# circle.net
KiCad netlist of a schematic drawn in EAGLE
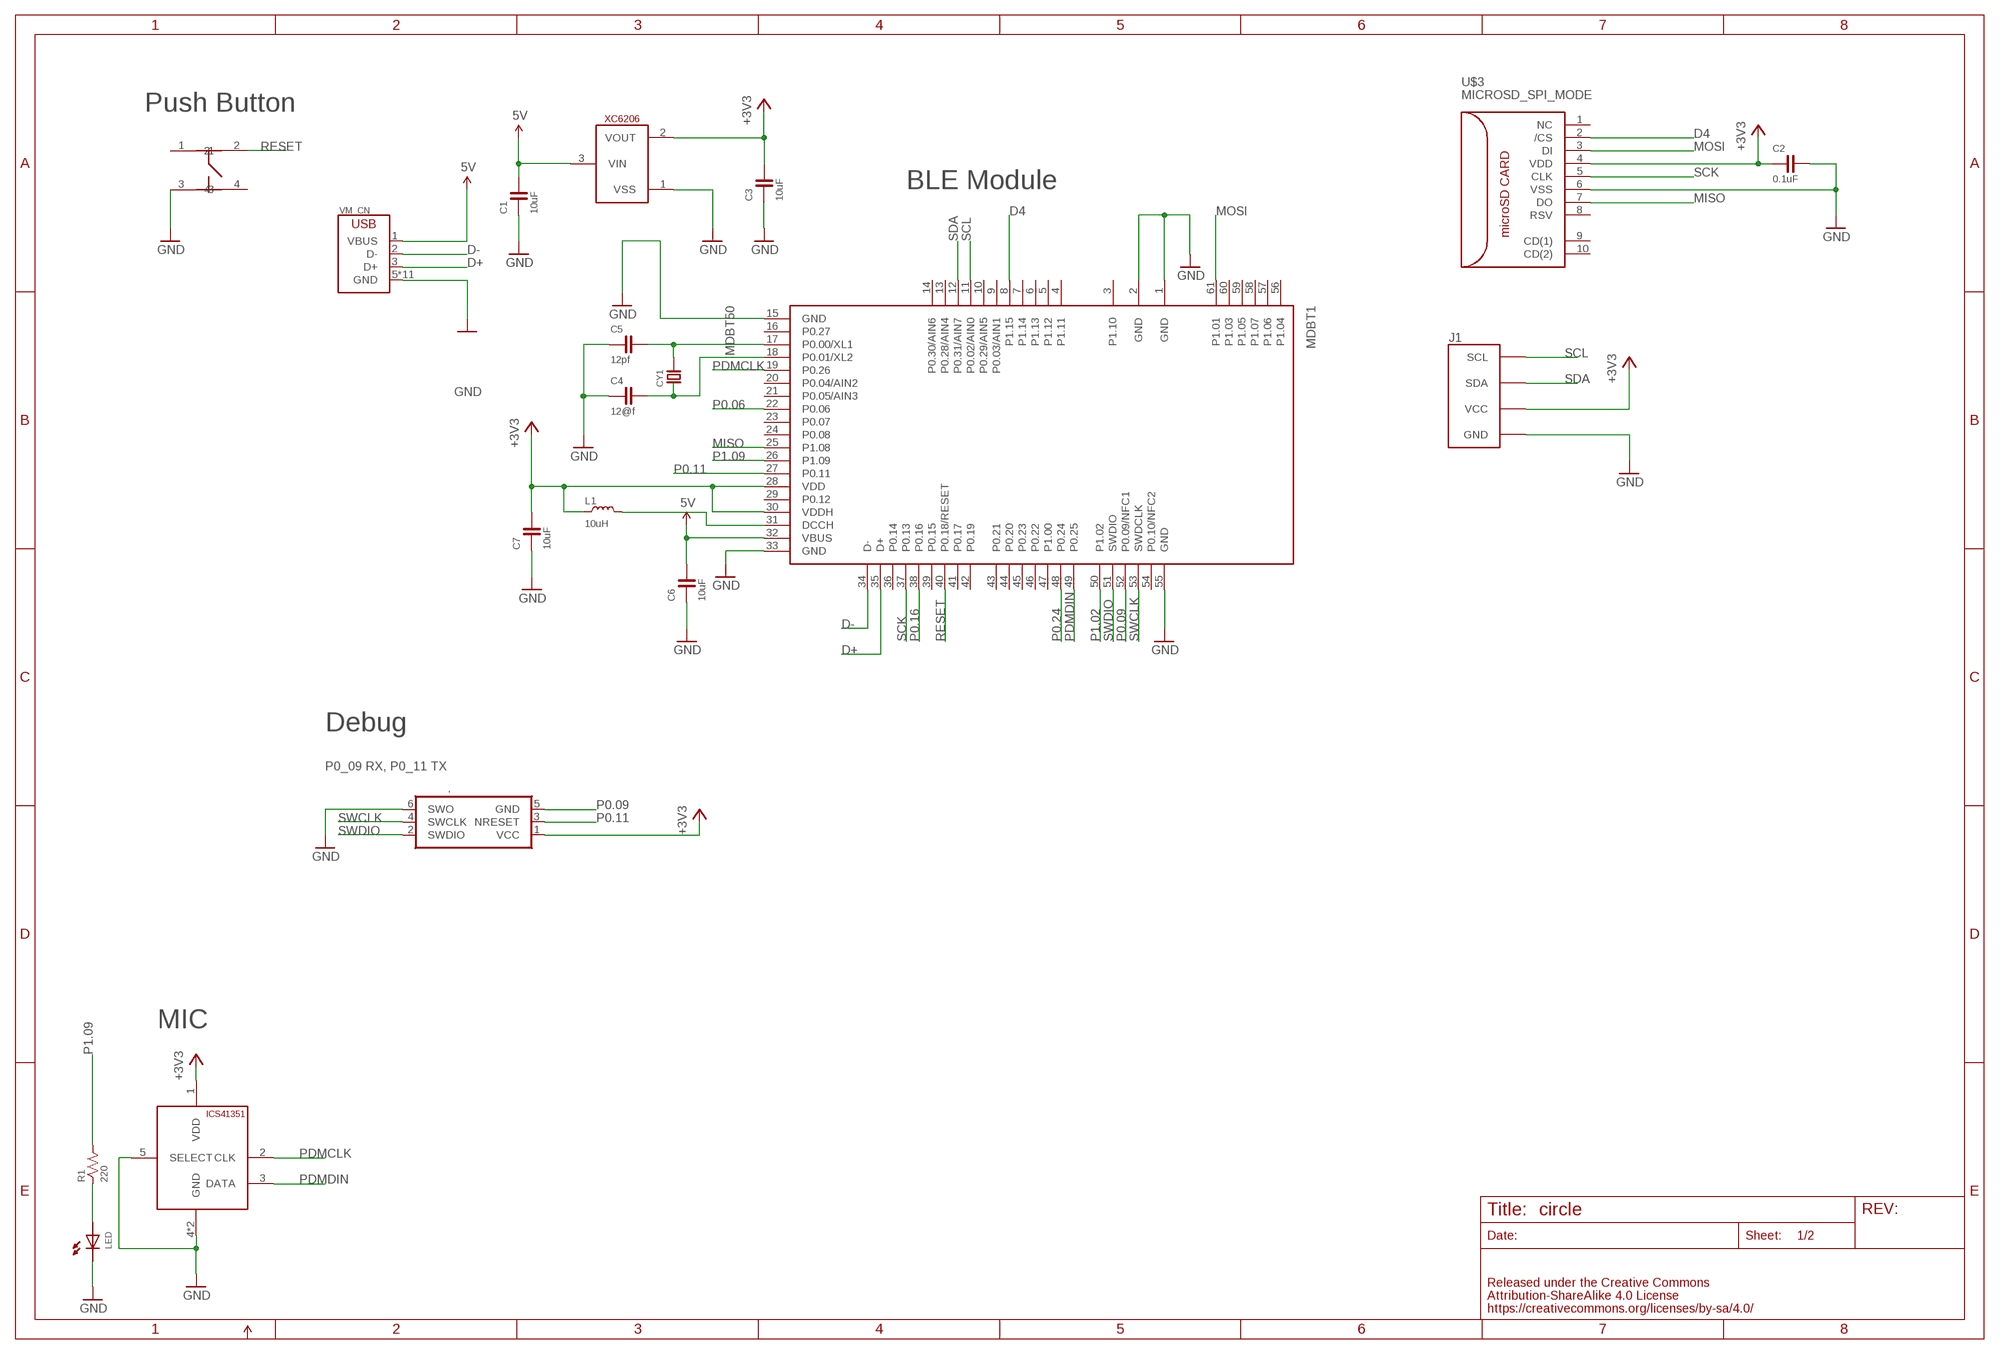
[diagram p0: schematic, sheet 1]
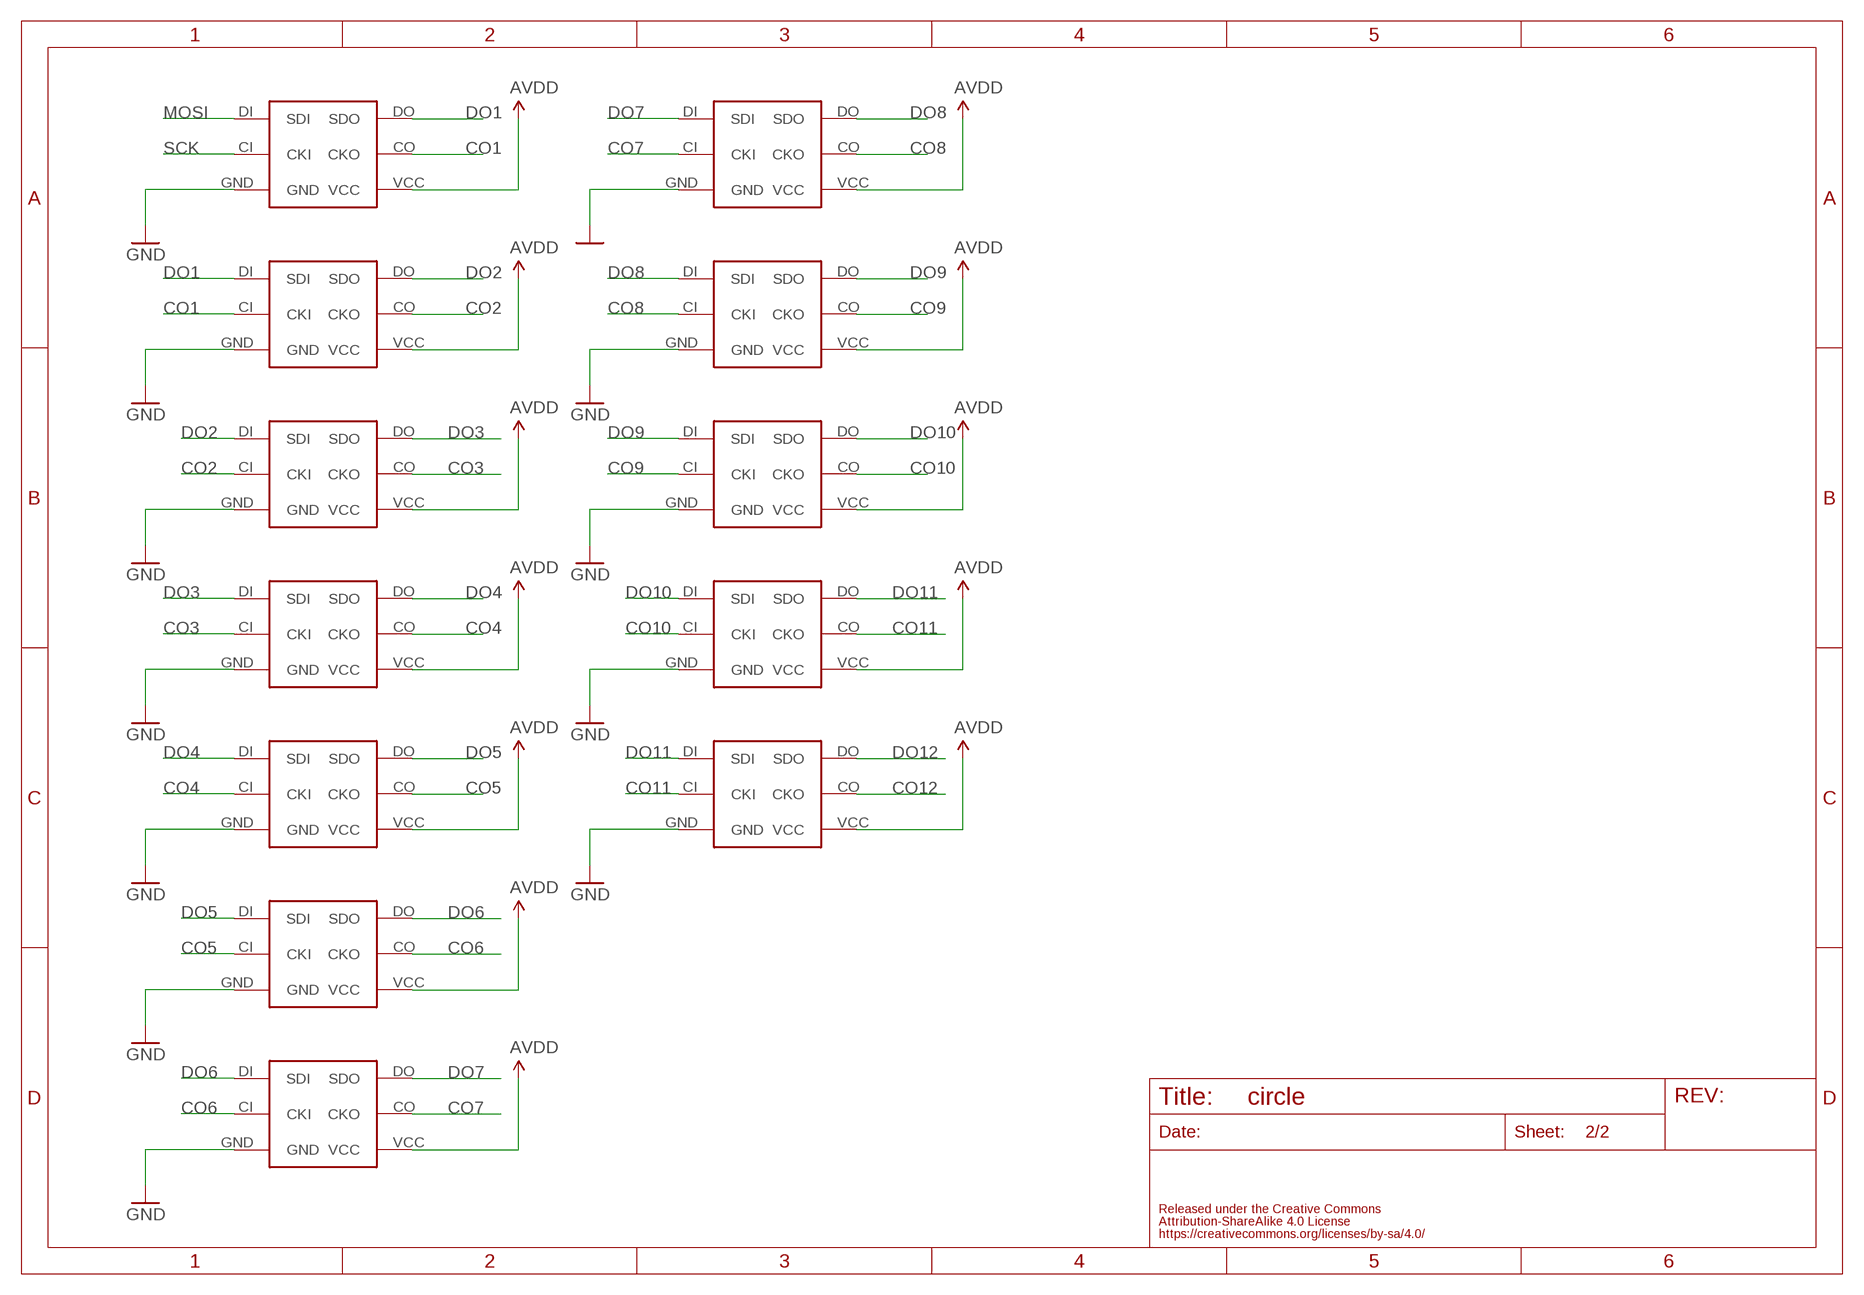
[diagram p1: schematic, sheet 2]

(export (version "E")
  (design (tool "Eeschema 10.0.6"))
  (components
    (comp (ref "0")
      (value "APA102_IPIXEL")
      (footprint "eagle-import:APA102(IPIXEL)")
      (libsource (lib "eagle-import") (part "APA102_IPIXEL"))
    )
    (comp (ref "1")
      (value "APA102_IPIXEL")
      (footprint "eagle-import:APA102(IPIXEL)")
      (libsource (lib "eagle-import") (part "APA102_IPIXEL"))
    )
    (comp (ref "2")
      (value "APA102_IPIXEL")
      (footprint "eagle-import:APA102(IPIXEL)")
      (libsource (lib "eagle-import") (part "APA102_IPIXEL"))
    )
    (comp (ref "3")
      (value "APA102_IPIXEL")
      (footprint "eagle-import:APA102(IPIXEL)")
      (libsource (lib "eagle-import") (part "APA102_IPIXEL"))
    )
    (comp (ref "4")
      (value "APA102_IPIXEL")
      (footprint "eagle-import:APA102(IPIXEL)")
      (libsource (lib "eagle-import") (part "APA102_IPIXEL"))
    )
    (comp (ref "5")
      (value "APA102_IPIXEL")
      (footprint "eagle-import:APA102(IPIXEL)")
      (libsource (lib "eagle-import") (part "APA102_IPIXEL"))
    )
    (comp (ref "6")
      (value "APA102_IPIXEL")
      (footprint "eagle-import:APA102(IPIXEL)")
      (libsource (lib "eagle-import") (part "APA102_IPIXEL"))
    )
    (comp (ref "7")
      (value "APA102_IPIXEL")
      (footprint "eagle-import:APA102(IPIXEL)")
      (libsource (lib "eagle-import") (part "APA102_IPIXEL"))
    )
    (comp (ref "8")
      (value "APA102_IPIXEL")
      (footprint "eagle-import:APA102(IPIXEL)")
      (libsource (lib "eagle-import") (part "APA102_IPIXEL"))
    )
    (comp (ref "9")
      (value "APA102_IPIXEL")
      (footprint "eagle-import:APA102(IPIXEL)")
      (libsource (lib "eagle-import") (part "APA102_IPIXEL"))
    )
    (comp (ref "10")
      (value "APA102_IPIXEL")
      (footprint "eagle-import:APA102(IPIXEL)")
      (libsource (lib "eagle-import") (part "APA102_IPIXEL"))
    )
    (comp (ref "11")
      (value "APA102_IPIXEL")
      (footprint "eagle-import:APA102(IPIXEL)")
      (libsource (lib "eagle-import") (part "APA102_IPIXEL"))
    )
    (comp (ref ".")
      (value "TC2030-IDC-NL")
      (footprint "eagle-import:TC2030-IDC-NL")
      (libsource (lib "eagle-import") (part "TC2030-IDC-NL"))
    )
    (comp (ref "C1")
      (value "10uF")
      (footprint "eagle-import:0603")
      (libsource (lib "eagle-import") (part "CAPACITOR-0603"))
    )
    (comp (ref "C2")
      (value "0.1uF")
      (footprint "eagle-import:0603")
      (libsource (lib "eagle-import") (part "CAPACITOR-0603"))
    )
    (comp (ref "C3")
      (value "10uF")
      (footprint "eagle-import:0603")
      (libsource (lib "eagle-import") (part "CAPACITOR-0603"))
    )
    (comp (ref "C4")
      (value "12@f")
      (footprint "eagle-import:0603")
      (libsource (lib "eagle-import") (part "CAPACITOR-0603"))
    )
    (comp (ref "C5")
      (value "12pf")
      (footprint "eagle-import:0603")
      (libsource (lib "eagle-import") (part "CAPACITOR-0603"))
    )
    (comp (ref "C6")
      (value "10uF")
      (footprint "eagle-import:0603")
      (libsource (lib "eagle-import") (part "CAPACITOR-0603"))
    )
    (comp (ref "C7")
      (value "10uF")
      (footprint "eagle-import:0603")
      (libsource (lib "eagle-import") (part "CAPACITOR-0603"))
    )
    (comp (ref "CY1")
      (value "CRYSTAL-ABS07")
      (footprint "eagle-import:ABRACON-ABS07-32.768KHZ")
      (libsource (lib "eagle-import") (part "CRYSTAL-ABS07"))
    )
    (comp (ref "IC1")
      (value "XC6206")
      (footprint "eagle-import:SOT-23")
      (libsource (lib "eagle-import") (part "XC6206"))
    )
    (comp (ref "J1")
      (value "FABO_BRICK_I2C-B04B-PASK-1")
      (footprint "eagle-import:FABO_BRICK_I2C_B04B-PASK-1")
      (libsource (lib "eagle-import") (part "FABO_BRICK_I2C-B04B-PASK-1"))
    )
    (comp (ref "L1")
      (value "10uH")
      (footprint "eagle-import:0603")
      (libsource (lib "eagle-import") (part "COIL-0603"))
    )
    (comp (ref "LED")
      (value "LED-0603")
      (footprint "eagle-import:0603")
      (libsource (lib "eagle-import") (part "LED-0603"))
    )
    (comp (ref "MDBT1")
      (value "MDBT50")
      (footprint "eagle-import:MDBT50")
      (libsource (lib "eagle-import") (part "MDBT50"))
    )
    (comp (ref "MIC1")
      (value "TDK-ICS41351")
      (footprint "eagle-import:ICS41351")
      (libsource (lib "eagle-import") (part "TDK-ICS41351"))
    )
    (comp (ref "R1")
      (value "220")
      (footprint "eagle-import:0603")
      (libsource (lib "eagle-import") (part "RESISTOR-0603"))
    )
    (comp (ref "U$3")
      (value "MICROSD_SPI_MODE")
      (footprint "eagle-import:MICRO_SD_CONNECTOR")
      (libsource (lib "eagle-import") (part "MICROSD_SPI_MODE"))
    )
    (comp (ref "U$5")
      (value "SWICTH-4P(KMR2)")
      (footprint "eagle-import:SWITCH-4P(KMR2)")
      (libsource (lib "eagle-import") (part "SWICTH-4P(KMR2)"))
    )
    (comp (ref "VM_CN")
      (value "USB-ZX62D")
      (footprint "eagle-import:ZX62D-B-5PA8")
      (libsource (lib "eagle-import") (part "USB-ZX62D"))
    )
  )
  (nets
    (net (code "1") (name "+3V3") (class "Default")
      (node (ref ".") (pin "1") (pinfunction "VCC_1") (pintype "passive"))
      (node (ref "C2") (pin "1") (pinfunction "1_1") (pintype "passive"))
      (node (ref "C3") (pin "2") (pinfunction "2_2") (pintype "passive"))
      (node (ref "C7") (pin "2") (pinfunction "2_2") (pintype "passive"))
      (node (ref "IC1") (pin "2") (pinfunction "VOUT_2") (pintype "bidirectional"))
      (node (ref "J1") (pin "VCC") (pinfunction "VCC_VCC") (pintype "bidirectional"))
      (node (ref "L1") (pin "1") (pinfunction "1_1") (pintype "bidirectional"))
      (node (ref "MDBT1") (pin "28") (pinfunction "VDD_28") (pintype "bidirectional"))
      (node (ref "MDBT1") (pin "30") (pinfunction "VDDH_30") (pintype "bidirectional"))
      (node (ref "MIC1") (pin "1") (pinfunction "VDD_1") (pintype "bidirectional"))
      (node (ref "U$3") (pin "4") (pinfunction "VDD_4") (pintype "bidirectional"))
    )
    (net (code "3") (name "5V") (class "Default")
      (node (ref "C1") (pin "2") (pinfunction "2_2") (pintype "passive"))
      (node (ref "C6") (pin "2") (pinfunction "2_2") (pintype "passive"))
      (node (ref "IC1") (pin "3") (pinfunction "VIN_3") (pintype "bidirectional"))
      (node (ref "MDBT1") (pin "32") (pinfunction "VBUS_32") (pintype "bidirectional"))
      (node (ref "VM_CN") (pin "1") (pinfunction "VBUS_1") (pintype "bidirectional"))
    )
    (net (code "4") (name "AVDD") (class "Default")
      (node (ref "0") (pin "VCC") (pinfunction "VCC_VCC") (pintype "bidirectional"))
      (node (ref "1") (pin "VCC") (pinfunction "VCC_VCC") (pintype "bidirectional"))
      (node (ref "10") (pin "VCC") (pinfunction "VCC_VCC") (pintype "bidirectional"))
      (node (ref "11") (pin "VCC") (pinfunction "VCC_VCC") (pintype "bidirectional"))
      (node (ref "2") (pin "VCC") (pinfunction "VCC_VCC") (pintype "bidirectional"))
      (node (ref "3") (pin "VCC") (pinfunction "VCC_VCC") (pintype "bidirectional"))
      (node (ref "4") (pin "VCC") (pinfunction "VCC_VCC") (pintype "bidirectional"))
      (node (ref "5") (pin "VCC") (pinfunction "VCC_VCC") (pintype "bidirectional"))
      (node (ref "6") (pin "VCC") (pinfunction "VCC_VCC") (pintype "bidirectional"))
      (node (ref "7") (pin "VCC") (pinfunction "VCC_VCC") (pintype "bidirectional"))
      (node (ref "8") (pin "VCC") (pinfunction "VCC_VCC") (pintype "bidirectional"))
      (node (ref "9") (pin "VCC") (pinfunction "VCC_VCC") (pintype "bidirectional"))
    )
    (net (code "5") (name "CO1") (class "Default")
      (node (ref "0") (pin "CO") (pinfunction "CKO_CO") (pintype "bidirectional"))
      (node (ref "1") (pin "CI") (pinfunction "CKI_CI") (pintype "bidirectional"))
    )
    (net (code "6") (name "CO2") (class "Default")
      (node (ref "1") (pin "CO") (pinfunction "CKO_CO") (pintype "bidirectional"))
      (node (ref "2") (pin "CI") (pinfunction "CKI_CI") (pintype "bidirectional"))
    )
    (net (code "7") (name "CO3") (class "Default")
      (node (ref "2") (pin "CO") (pinfunction "CKO_CO") (pintype "bidirectional"))
      (node (ref "3") (pin "CI") (pinfunction "CKI_CI") (pintype "bidirectional"))
    )
    (net (code "8") (name "CO4") (class "Default")
      (node (ref "3") (pin "CO") (pinfunction "CKO_CO") (pintype "bidirectional"))
      (node (ref "4") (pin "CI") (pinfunction "CKI_CI") (pintype "bidirectional"))
    )
    (net (code "9") (name "CO5") (class "Default")
      (node (ref "4") (pin "CO") (pinfunction "CKO_CO") (pintype "bidirectional"))
      (node (ref "5") (pin "CI") (pinfunction "CKI_CI") (pintype "bidirectional"))
    )
    (net (code "10") (name "CO6") (class "Default")
      (node (ref "5") (pin "CO") (pinfunction "CKO_CO") (pintype "bidirectional"))
      (node (ref "6") (pin "CI") (pinfunction "CKI_CI") (pintype "bidirectional"))
    )
    (net (code "11") (name "CO7") (class "Default")
      (node (ref "6") (pin "CO") (pinfunction "CKO_CO") (pintype "bidirectional"))
      (node (ref "7") (pin "CI") (pinfunction "CKI_CI") (pintype "bidirectional"))
    )
    (net (code "12") (name "CO8") (class "Default")
      (node (ref "7") (pin "CO") (pinfunction "CKO_CO") (pintype "bidirectional"))
      (node (ref "8") (pin "CI") (pinfunction "CKI_CI") (pintype "bidirectional"))
    )
    (net (code "13") (name "CO9") (class "Default")
      (node (ref "8") (pin "CO") (pinfunction "CKO_CO") (pintype "bidirectional"))
      (node (ref "9") (pin "CI") (pinfunction "CKI_CI") (pintype "bidirectional"))
    )
    (net (code "14") (name "CO10") (class "Default")
      (node (ref "10") (pin "CI") (pinfunction "CKI_CI") (pintype "bidirectional"))
      (node (ref "9") (pin "CO") (pinfunction "CKO_CO") (pintype "bidirectional"))
    )
    (net (code "15") (name "CO11") (class "Default")
      (node (ref "10") (pin "CO") (pinfunction "CKO_CO") (pintype "bidirectional"))
      (node (ref "11") (pin "CI") (pinfunction "CKI_CI") (pintype "bidirectional"))
    )
    (net (code "16") (name "CO12") (class "Default")
      (node (ref "11") (pin "CO") (pinfunction "CKO_CO") (pintype "bidirectional"))
    )
    (net (code "17") (name "D+") (class "Default")
      (node (ref "MDBT1") (pin "35") (pinfunction "D+_35") (pintype "bidirectional"))
      (node (ref "VM_CN") (pin "3") (pinfunction "D+_3") (pintype "bidirectional"))
    )
    (net (code "18") (name "D-") (class "Default")
      (node (ref "MDBT1") (pin "34") (pinfunction "D-_34") (pintype "bidirectional"))
      (node (ref "VM_CN") (pin "2") (pinfunction "D-_2") (pintype "bidirectional"))
    )
    (net (code "19") (name "D4") (class "Default")
      (node (ref "MDBT1") (pin "8") (pinfunction "P1.15_8") (pintype "bidirectional"))
      (node (ref "U$3") (pin "2") (pinfunction "/CS_2") (pintype "bidirectional"))
    )
    (net (code "20") (name "DO1") (class "Default")
      (node (ref "0") (pin "DO") (pinfunction "SDO_DO") (pintype "bidirectional"))
      (node (ref "1") (pin "DI") (pinfunction "SDI_DI") (pintype "bidirectional"))
    )
    (net (code "21") (name "DO2") (class "Default")
      (node (ref "1") (pin "DO") (pinfunction "SDO_DO") (pintype "bidirectional"))
      (node (ref "2") (pin "DI") (pinfunction "SDI_DI") (pintype "bidirectional"))
    )
    (net (code "22") (name "DO3") (class "Default")
      (node (ref "2") (pin "DO") (pinfunction "SDO_DO") (pintype "bidirectional"))
      (node (ref "3") (pin "DI") (pinfunction "SDI_DI") (pintype "bidirectional"))
    )
    (net (code "23") (name "DO4") (class "Default")
      (node (ref "3") (pin "DO") (pinfunction "SDO_DO") (pintype "bidirectional"))
      (node (ref "4") (pin "DI") (pinfunction "SDI_DI") (pintype "bidirectional"))
    )
    (net (code "24") (name "DO5") (class "Default")
      (node (ref "4") (pin "DO") (pinfunction "SDO_DO") (pintype "bidirectional"))
      (node (ref "5") (pin "DI") (pinfunction "SDI_DI") (pintype "bidirectional"))
    )
    (net (code "25") (name "DO6") (class "Default")
      (node (ref "5") (pin "DO") (pinfunction "SDO_DO") (pintype "bidirectional"))
      (node (ref "6") (pin "DI") (pinfunction "SDI_DI") (pintype "bidirectional"))
    )
    (net (code "26") (name "DO7") (class "Default")
      (node (ref "6") (pin "DO") (pinfunction "SDO_DO") (pintype "bidirectional"))
      (node (ref "7") (pin "DI") (pinfunction "SDI_DI") (pintype "bidirectional"))
    )
    (net (code "27") (name "DO8") (class "Default")
      (node (ref "7") (pin "DO") (pinfunction "SDO_DO") (pintype "bidirectional"))
      (node (ref "8") (pin "DI") (pinfunction "SDI_DI") (pintype "bidirectional"))
    )
    (net (code "28") (name "DO9") (class "Default")
      (node (ref "8") (pin "DO") (pinfunction "SDO_DO") (pintype "bidirectional"))
      (node (ref "9") (pin "DI") (pinfunction "SDI_DI") (pintype "bidirectional"))
    )
    (net (code "29") (name "DO10") (class "Default")
      (node (ref "10") (pin "DI") (pinfunction "SDI_DI") (pintype "bidirectional"))
      (node (ref "9") (pin "DO") (pinfunction "SDO_DO") (pintype "bidirectional"))
    )
    (net (code "30") (name "DO11") (class "Default")
      (node (ref "10") (pin "DO") (pinfunction "SDO_DO") (pintype "bidirectional"))
      (node (ref "11") (pin "DI") (pinfunction "SDI_DI") (pintype "bidirectional"))
    )
    (net (code "31") (name "DO12") (class "Default")
      (node (ref "11") (pin "DO") (pinfunction "SDO_DO") (pintype "bidirectional"))
    )
    (net (code "32") (name "GND") (class "Default")
      (node (ref ".") (pin "6") (pinfunction "SWO_6") (pintype "passive"))
      (node (ref "0") (pin "GND") (pinfunction "GND_GND") (pintype "bidirectional"))
      (node (ref "1") (pin "GND") (pinfunction "GND_GND") (pintype "bidirectional"))
      (node (ref "10") (pin "GND") (pinfunction "GND_GND") (pintype "bidirectional"))
      (node (ref "11") (pin "GND") (pinfunction "GND_GND") (pintype "bidirectional"))
      (node (ref "2") (pin "GND") (pinfunction "GND_GND") (pintype "bidirectional"))
      (node (ref "3") (pin "GND") (pinfunction "GND_GND") (pintype "bidirectional"))
      (node (ref "4") (pin "GND") (pinfunction "GND_GND") (pintype "bidirectional"))
      (node (ref "5") (pin "GND") (pinfunction "GND_GND") (pintype "bidirectional"))
      (node (ref "6") (pin "GND") (pinfunction "GND_GND") (pintype "bidirectional"))
      (node (ref "7") (pin "GND") (pinfunction "GND_GND") (pintype "bidirectional"))
      (node (ref "8") (pin "GND") (pinfunction "GND_GND") (pintype "bidirectional"))
      (node (ref "9") (pin "GND") (pinfunction "GND_GND") (pintype "bidirectional"))
      (node (ref "C1") (pin "1") (pinfunction "1_1") (pintype "passive"))
      (node (ref "C2") (pin "2") (pinfunction "2_2") (pintype "passive"))
      (node (ref "C3") (pin "1") (pinfunction "1_1") (pintype "passive"))
      (node (ref "C4") (pin "1") (pinfunction "1_1") (pintype "passive"))
      (node (ref "C5") (pin "1") (pinfunction "1_1") (pintype "passive"))
      (node (ref "C6") (pin "1") (pinfunction "1_1") (pintype "passive"))
      (node (ref "C7") (pin "1") (pinfunction "1_1") (pintype "passive"))
      (node (ref "IC1") (pin "1") (pinfunction "VSS_1") (pintype "bidirectional"))
      (node (ref "J1") (pin "GND") (pinfunction "GND_GND") (pintype "bidirectional"))
      (node (ref "LED") (pin "CATHODE") (pinfunction "CATHODE_CATHODE") (pintype "passive"))
      (node (ref "MDBT1") (pin "1") (pinfunction "GND_1") (pintype "bidirectional"))
      (node (ref "MDBT1") (pin "15") (pinfunction "GND_15") (pintype "bidirectional"))
      (node (ref "MDBT1") (pin "2") (pinfunction "GND_2") (pintype "bidirectional"))
      (node (ref "MDBT1") (pin "33") (pinfunction "GND_33") (pintype "bidirectional"))
      (node (ref "MDBT1") (pin "55") (pinfunction "GND_55") (pintype "bidirectional"))
      (node (ref "MIC1") (pin "4") (pinfunction "GND_4") (pintype "bidirectional"))
      (node (ref "MIC1") (pin "5") (pinfunction "SELECT_5") (pintype "bidirectional"))
      (node (ref "MIC1") (pin "6") (pinfunction "GND_6") (pintype "bidirectional"))
      (node (ref "U$3") (pin "6") (pinfunction "VSS_6") (pintype "bidirectional"))
      (node (ref "U$5") (pin "3") (pinfunction "3_3") (pintype "bidirectional"))
      (node (ref "VM_CN") (pin "5") (pinfunction "GND_5") (pintype "bidirectional"))
      (node (ref "VM_CN") (pin "B1") (pinfunction "GND_B1") (pintype "bidirectional"))
      (node (ref "VM_CN") (pin "B2") (pinfunction "GND_B2") (pintype "bidirectional"))
      (node (ref "VM_CN") (pin "B3") (pinfunction "GND_B3") (pintype "bidirectional"))
      (node (ref "VM_CN") (pin "B4") (pinfunction "GND_B4") (pintype "bidirectional"))
      (node (ref "VM_CN") (pin "T1") (pinfunction "GND_T1") (pintype "bidirectional"))
      (node (ref "VM_CN") (pin "T2") (pinfunction "GND_T2") (pintype "bidirectional"))
      (node (ref "VM_CN") (pin "T3") (pinfunction "GND_T3") (pintype "bidirectional"))
      (node (ref "VM_CN") (pin "T4") (pinfunction "GND_T4") (pintype "bidirectional"))
      (node (ref "VM_CN") (pin "T5") (pinfunction "GND_T5") (pintype "bidirectional"))
      (node (ref "VM_CN") (pin "T6") (pinfunction "GND_T6") (pintype "bidirectional"))
    )
    (net (code "33") (name "MISO") (class "Default")
      (node (ref "MDBT1") (pin "25") (pinfunction "P1.08_25") (pintype "bidirectional"))
      (node (ref "U$3") (pin "7") (pinfunction "DO_7") (pintype "bidirectional"))
    )
    (net (code "34") (name "MOSI") (class "Default")
      (node (ref "0") (pin "DI") (pinfunction "SDI_DI") (pintype "bidirectional"))
      (node (ref "MDBT1") (pin "61") (pinfunction "P1.01_61") (pintype "bidirectional"))
      (node (ref "U$3") (pin "3") (pinfunction "DI_3") (pintype "bidirectional"))
    )
    (net (code "35") (name "Net-(LED-PadANODE)") (class "Default")
      (node (ref "LED") (pin "ANODE") (pinfunction "ANODE_ANODE") (pintype "passive"))
      (node (ref "R1") (pin "1") (pinfunction "1_1") (pintype "bidirectional"))
    )
    (net (code "36") (name "Net-(MDBT1-DCCH)") (class "Default")
      (node (ref "L1") (pin "2") (pinfunction "2_2") (pintype "bidirectional"))
      (node (ref "MDBT1") (pin "31") (pinfunction "DCCH_31") (pintype "bidirectional"))
    )
    (net (code "37") (name "Net-(MDBT1-P0.00{slash}XL1)") (class "Default")
      (node (ref "C5") (pin "2") (pinfunction "2_2") (pintype "passive"))
      (node (ref "CY1") (pin "P$2") (pinfunction "P$2_P$2") (pintype "bidirectional"))
      (node (ref "MDBT1") (pin "17") (pinfunction "P0.00/XL1_17") (pintype "bidirectional"))
    )
    (net (code "38") (name "Net-(MDBT1-P0.01{slash}XL2)") (class "Default")
      (node (ref "C4") (pin "2") (pinfunction "2_2") (pintype "passive"))
      (node (ref "CY1") (pin "P$1") (pinfunction "P$1_P$1") (pintype "bidirectional"))
      (node (ref "MDBT1") (pin "18") (pinfunction "P0.01/XL2_18") (pintype "bidirectional"))
    )
    (net (code "39") (name "P0.06") (class "Default")
      (node (ref "MDBT1") (pin "22") (pinfunction "P0.06_22") (pintype "bidirectional"))
    )
    (net (code "40") (name "P0.09") (class "Default")
      (node (ref ".") (pin "5") (pinfunction "GND_5") (pintype "passive"))
      (node (ref "MDBT1") (pin "52") (pinfunction "P0.09/NFC1_52") (pintype "bidirectional"))
    )
    (net (code "41") (name "P0.11") (class "Default")
      (node (ref ".") (pin "3") (pinfunction "NRESET_3") (pintype "passive"))
      (node (ref "MDBT1") (pin "27") (pinfunction "P0.11_27") (pintype "bidirectional"))
    )
    (net (code "42") (name "P0.16") (class "Default")
      (node (ref "MDBT1") (pin "38") (pinfunction "P0.16_38") (pintype "bidirectional"))
    )
    (net (code "43") (name "P0.24") (class "Default")
      (node (ref "MDBT1") (pin "48") (pinfunction "P0.24_48") (pintype "bidirectional"))
    )
    (net (code "44") (name "P1.02") (class "Default")
      (node (ref "MDBT1") (pin "50") (pinfunction "P1.02_50") (pintype "bidirectional"))
    )
    (net (code "45") (name "P1.09") (class "Default")
      (node (ref "MDBT1") (pin "26") (pinfunction "P1.09_26") (pintype "bidirectional"))
      (node (ref "R1") (pin "2") (pinfunction "2_2") (pintype "bidirectional"))
    )
    (net (code "46") (name "PDMCLK") (class "Default")
      (node (ref "MDBT1") (pin "19") (pinfunction "P0.26_19") (pintype "bidirectional"))
      (node (ref "MIC1") (pin "2") (pinfunction "CLK_2") (pintype "bidirectional"))
    )
    (net (code "47") (name "PDMDIN") (class "Default")
      (node (ref "MDBT1") (pin "49") (pinfunction "P0.25_49") (pintype "bidirectional"))
      (node (ref "MIC1") (pin "3") (pinfunction "DATA_3") (pintype "bidirectional"))
    )
    (net (code "48") (name "RESET") (class "Default")
      (node (ref "MDBT1") (pin "40") (pinfunction "P0.18/RESET_40") (pintype "bidirectional"))
      (node (ref "U$5") (pin "2") (pinfunction "2_2") (pintype "bidirectional"))
    )
    (net (code "49") (name "SCK") (class "Default")
      (node (ref "0") (pin "CI") (pinfunction "CKI_CI") (pintype "bidirectional"))
      (node (ref "MDBT1") (pin "37") (pinfunction "P0.13_37") (pintype "bidirectional"))
      (node (ref "U$3") (pin "5") (pinfunction "CLK_5") (pintype "bidirectional"))
    )
    (net (code "50") (name "SCL") (class "Default")
      (node (ref "J1") (pin "SCL") (pinfunction "SCL_SCL") (pintype "bidirectional"))
      (node (ref "MDBT1") (pin "11") (pinfunction "P0.02/AIN0_11") (pintype "bidirectional"))
    )
    (net (code "51") (name "SDA") (class "Default")
      (node (ref "J1") (pin "SDA") (pinfunction "SDA_SDA") (pintype "bidirectional"))
      (node (ref "MDBT1") (pin "12") (pinfunction "P0.31/AIN7_12") (pintype "bidirectional"))
    )
    (net (code "52") (name "SWCLK") (class "Default")
      (node (ref ".") (pin "4") (pinfunction "SWCLK_4") (pintype "passive"))
      (node (ref "MDBT1") (pin "53") (pinfunction "SWDCLK_53") (pintype "bidirectional"))
    )
    (net (code "53") (name "SWDIO") (class "Default")
      (node (ref ".") (pin "2") (pinfunction "SWDIO_2") (pintype "passive"))
      (node (ref "MDBT1") (pin "51") (pinfunction "SWDIO_51") (pintype "bidirectional"))
    )
    (net (code "54") (name "unconnected-(MDBT1-P0.03{slash}AIN1-Pad9)") (class "Default")
      (node (ref "MDBT1") (pin "9") (pinfunction "P0.03/AIN1_9") (pintype "bidirectional"))
    )
    (net (code "55") (name "unconnected-(MDBT1-P0.04{slash}AIN2-Pad20)") (class "Default")
      (node (ref "MDBT1") (pin "20") (pinfunction "P0.04/AIN2_20") (pintype "bidirectional"))
    )
    (net (code "56") (name "unconnected-(MDBT1-P0.05{slash}AIN3-Pad21)") (class "Default")
      (node (ref "MDBT1") (pin "21") (pinfunction "P0.05/AIN3_21") (pintype "bidirectional"))
    )
    (net (code "57") (name "unconnected-(MDBT1-P0.07-Pad23)") (class "Default")
      (node (ref "MDBT1") (pin "23") (pinfunction "P0.07_23") (pintype "bidirectional"))
    )
    (net (code "58") (name "unconnected-(MDBT1-P0.08-Pad24)") (class "Default")
      (node (ref "MDBT1") (pin "24") (pinfunction "P0.08_24") (pintype "bidirectional"))
    )
    (net (code "59") (name "unconnected-(MDBT1-P0.10{slash}NFC2-Pad54)") (class "Default")
      (node (ref "MDBT1") (pin "54") (pinfunction "P0.10/NFC2_54") (pintype "bidirectional"))
    )
    (net (code "60") (name "unconnected-(MDBT1-P0.12-Pad29)") (class "Default")
      (node (ref "MDBT1") (pin "29") (pinfunction "P0.12_29") (pintype "bidirectional"))
    )
    (net (code "61") (name "unconnected-(MDBT1-P0.14-Pad36)") (class "Default")
      (node (ref "MDBT1") (pin "36") (pinfunction "P0.14_36") (pintype "bidirectional"))
    )
    (net (code "62") (name "unconnected-(MDBT1-P0.15-Pad39)") (class "Default")
      (node (ref "MDBT1") (pin "39") (pinfunction "P0.15_39") (pintype "bidirectional"))
    )
    (net (code "63") (name "unconnected-(MDBT1-P0.17-Pad41)") (class "Default")
      (node (ref "MDBT1") (pin "41") (pinfunction "P0.17_41") (pintype "bidirectional"))
    )
    (net (code "64") (name "unconnected-(MDBT1-P0.19-Pad42)") (class "Default")
      (node (ref "MDBT1") (pin "42") (pinfunction "P0.19_42") (pintype "bidirectional"))
    )
    (net (code "65") (name "unconnected-(MDBT1-P0.20-Pad44)") (class "Default")
      (node (ref "MDBT1") (pin "44") (pinfunction "P0.20_44") (pintype "bidirectional"))
    )
    (net (code "66") (name "unconnected-(MDBT1-P0.21-Pad43)") (class "Default")
      (node (ref "MDBT1") (pin "43") (pinfunction "P0.21_43") (pintype "bidirectional"))
    )
    (net (code "67") (name "unconnected-(MDBT1-P0.22-Pad46)") (class "Default")
      (node (ref "MDBT1") (pin "46") (pinfunction "P0.22_46") (pintype "bidirectional"))
    )
    (net (code "68") (name "unconnected-(MDBT1-P0.23-Pad45)") (class "Default")
      (node (ref "MDBT1") (pin "45") (pinfunction "P0.23_45") (pintype "bidirectional"))
    )
    (net (code "69") (name "unconnected-(MDBT1-P0.27-Pad16)") (class "Default")
      (node (ref "MDBT1") (pin "16") (pinfunction "P0.27_16") (pintype "bidirectional"))
    )
    (net (code "70") (name "unconnected-(MDBT1-P0.28{slash}AIN4-Pad13)") (class "Default")
      (node (ref "MDBT1") (pin "13") (pinfunction "P0.28/AIN4_13") (pintype "bidirectional"))
    )
    (net (code "71") (name "unconnected-(MDBT1-P0.29{slash}AIN5-Pad10)") (class "Default")
      (node (ref "MDBT1") (pin "10") (pinfunction "P0.29/AIN5_10") (pintype "bidirectional"))
    )
    (net (code "72") (name "unconnected-(MDBT1-P0.30{slash}AIN6-Pad14)") (class "Default")
      (node (ref "MDBT1") (pin "14") (pinfunction "P0.30/AIN6_14") (pintype "bidirectional"))
    )
    (net (code "73") (name "unconnected-(MDBT1-P1.00-Pad47)") (class "Default")
      (node (ref "MDBT1") (pin "47") (pinfunction "P1.00_47") (pintype "bidirectional"))
    )
    (net (code "74") (name "unconnected-(MDBT1-P1.03-Pad60)") (class "Default")
      (node (ref "MDBT1") (pin "60") (pinfunction "P1.03_60") (pintype "bidirectional"))
    )
    (net (code "75") (name "unconnected-(MDBT1-P1.04-Pad56)") (class "Default")
      (node (ref "MDBT1") (pin "56") (pinfunction "P1.04_56") (pintype "bidirectional"))
    )
    (net (code "76") (name "unconnected-(MDBT1-P1.05-Pad59)") (class "Default")
      (node (ref "MDBT1") (pin "59") (pinfunction "P1.05_59") (pintype "bidirectional"))
    )
    (net (code "77") (name "unconnected-(MDBT1-P1.06-Pad57)") (class "Default")
      (node (ref "MDBT1") (pin "57") (pinfunction "P1.06_57") (pintype "bidirectional"))
    )
    (net (code "78") (name "unconnected-(MDBT1-P1.07-Pad58)") (class "Default")
      (node (ref "MDBT1") (pin "58") (pinfunction "P1.07_58") (pintype "bidirectional"))
    )
    (net (code "79") (name "unconnected-(MDBT1-P1.10-Pad3)") (class "Default")
      (node (ref "MDBT1") (pin "3") (pinfunction "P1.10_3") (pintype "bidirectional"))
    )
    (net (code "80") (name "unconnected-(MDBT1-P1.11-Pad4)") (class "Default")
      (node (ref "MDBT1") (pin "4") (pinfunction "P1.11_4") (pintype "bidirectional"))
    )
    (net (code "81") (name "unconnected-(MDBT1-P1.12-Pad5)") (class "Default")
      (node (ref "MDBT1") (pin "5") (pinfunction "P1.12_5") (pintype "bidirectional"))
    )
    (net (code "82") (name "unconnected-(MDBT1-P1.13-Pad6)") (class "Default")
      (node (ref "MDBT1") (pin "6") (pinfunction "P1.13_6") (pintype "bidirectional"))
    )
    (net (code "83") (name "unconnected-(MDBT1-P1.14-Pad7)") (class "Default")
      (node (ref "MDBT1") (pin "7") (pinfunction "P1.14_7") (pintype "bidirectional"))
    )
    (net (code "84") (name "unconnected-(U$3-CD(1)-Pad9)") (class "Default")
      (node (ref "U$3") (pin "9") (pinfunction "CD(1)_9") (pintype "bidirectional"))
    )
    (net (code "85") (name "unconnected-(U$3-CD(2)-Pad10)") (class "Default")
      (node (ref "U$3") (pin "10") (pinfunction "CD(2)_10") (pintype "bidirectional"))
    )
    (net (code "86") (name "unconnected-(U$3-NC-Pad1)") (class "Default")
      (node (ref "U$3") (pin "1") (pinfunction "NC_1") (pintype "bidirectional"))
    )
    (net (code "87") (name "unconnected-(U$3-RSV-Pad8)") (class "Default")
      (node (ref "U$3") (pin "8") (pinfunction "RSV_8") (pintype "bidirectional"))
    )
    (net (code "88") (name "unconnected-(U$5-Pad1)") (class "Default")
      (node (ref "U$5") (pin "1") (pinfunction "1_1") (pintype "bidirectional"))
    )
    (net (code "89") (name "unconnected-(U$5-Pad4)") (class "Default")
      (node (ref "U$5") (pin "4") (pinfunction "4_4") (pintype "bidirectional"))
    )
  )
)
